# my_gearbox_project.net
KiCad netlist of a schematic drawn in EAGLE
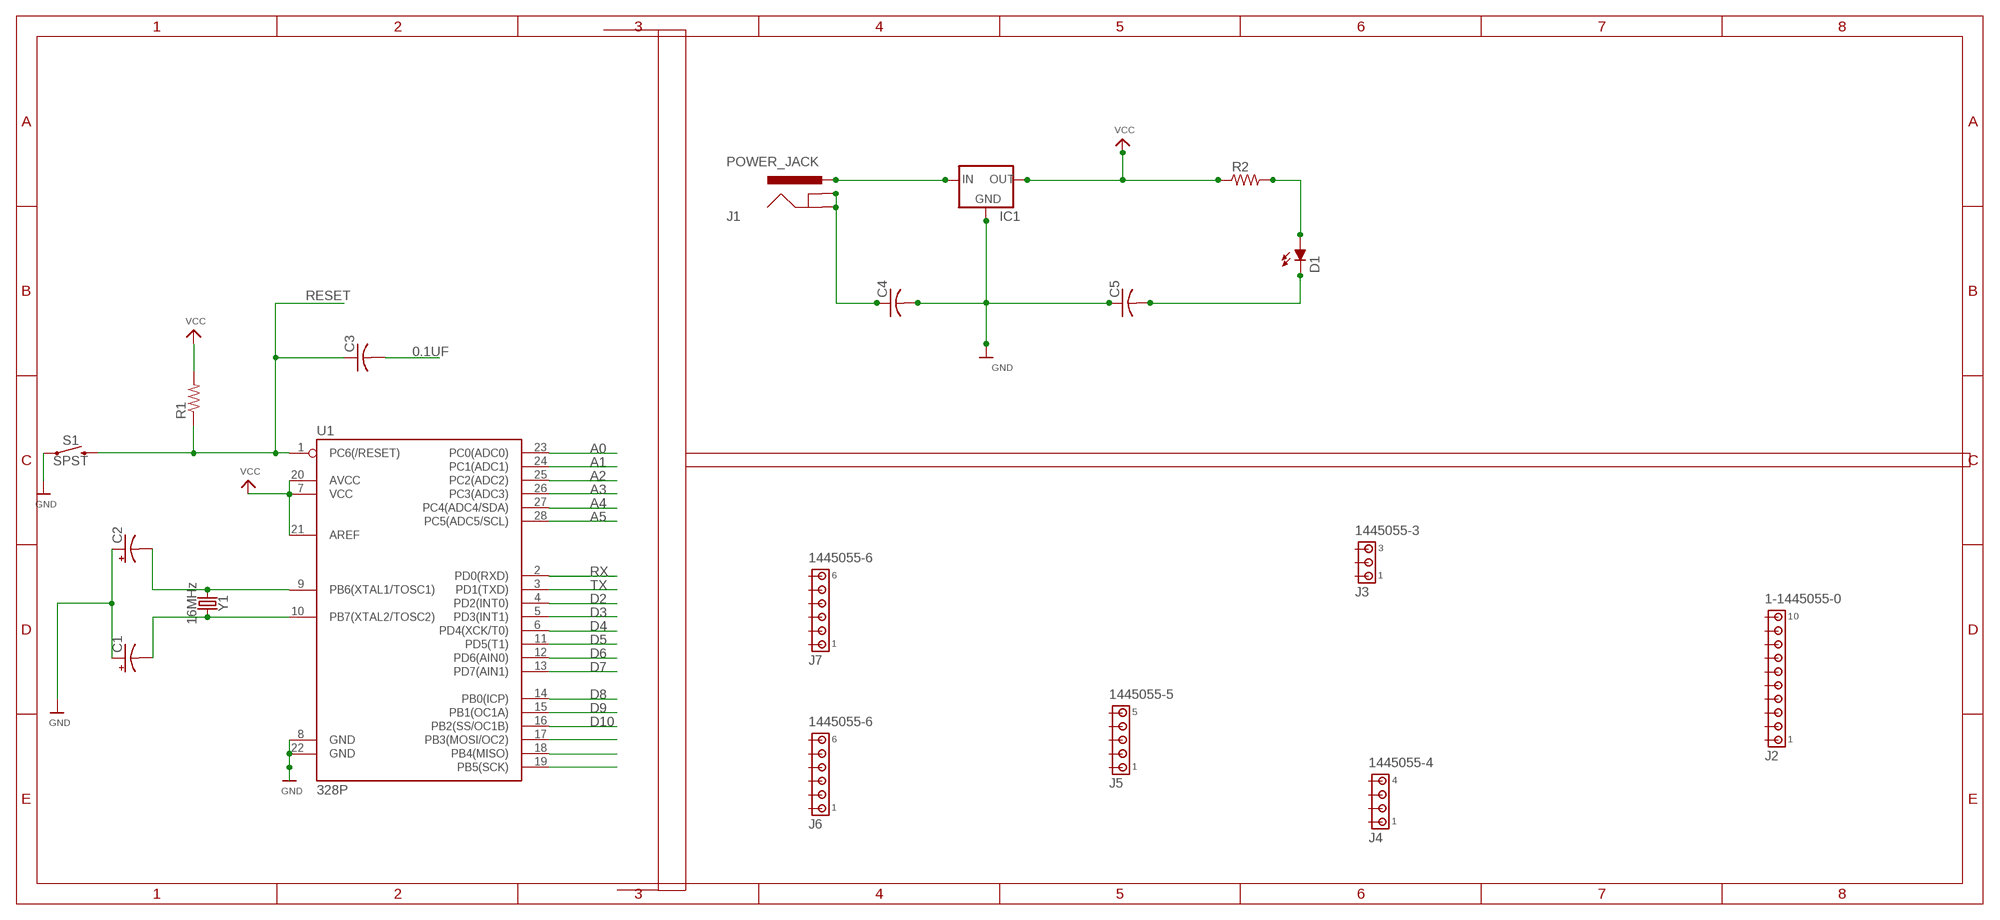
[diagram p0: schematic, sheet 1]

(export (version "E")
  (design (tool "Eeschema 10.0.6"))
  (components
    (comp (ref "C1")
      (value "CPOL-USE10-30")
      (footprint "eagle-import:EB30D")
      (libsource (lib "eagle-import") (part "CPOL-USE10-30"))
    )
    (comp (ref "C2")
      (value "CPOL-USE10-30")
      (footprint "eagle-import:EB30D")
      (libsource (lib "eagle-import") (part "CPOL-USE10-30"))
    )
    (comp (ref "C3")
      (value "C-US050-075X075")
      (footprint "eagle-import:C050-075X075")
      (libsource (lib "eagle-import") (part "C-US050-075X075"))
    )
    (comp (ref "C4")
      (value "C-US025-030X050")
      (footprint "eagle-import:C025-030X050")
      (libsource (lib "eagle-import") (part "C-US025-030X050"))
    )
    (comp (ref "C5")
      (value "C-US025-030X050")
      (footprint "eagle-import:C025-030X050")
      (libsource (lib "eagle-import") (part "C-US025-030X050"))
    )
    (comp (ref "D1")
      (value "LED_LEDCHIP-LED0603MP")
      (footprint "eagle-import:LED_CHIP-LED0603MP")
      (libsource (lib "eagle-import") (part "LED_LEDCHIP-LED0603MP"))
    )
    (comp (ref "IC1")
      (value "MCP1700INLINE")
      (footprint "eagle-import:TO92-INLINE")
      (libsource (lib "eagle-import") (part "MCP1700INLINE"))
    )
    (comp (ref "J1")
      (value "POWER_JACK")
      (footprint "eagle-import:POWER_JACK_PTH")
      (libsource (lib "eagle-import") (part "POWER_JACK"))
    )
    (comp (ref "J2")
      (value "1-1445055-0")
      (footprint "eagle-import:1445055-10")
      (libsource (lib "eagle-import") (part "1-1445055-0"))
    )
    (comp (ref "J3")
      (value "1445055-3")
      (footprint "eagle-import:1445055-3")
      (libsource (lib "eagle-import") (part "1445055-3"))
    )
    (comp (ref "J4")
      (value "1445055-4")
      (footprint "eagle-import:1445055-4")
      (libsource (lib "eagle-import") (part "1445055-4"))
    )
    (comp (ref "J5")
      (value "1445055-5")
      (footprint "eagle-import:1445055-5")
      (libsource (lib "eagle-import") (part "1445055-5"))
    )
    (comp (ref "J6")
      (value "1445055-6")
      (footprint "eagle-import:1445055-6")
      (libsource (lib "eagle-import") (part "1445055-6"))
    )
    (comp (ref "J7")
      (value "1445055-6")
      (footprint "eagle-import:1445055-6")
      (libsource (lib "eagle-import") (part "1445055-6"))
    )
    (comp (ref "R1")
      (value "R-US_R0402")
      (footprint "eagle-import:R0402")
      (libsource (lib "eagle-import") (part "R-US_R0402"))
    )
    (comp (ref "R2")
      (value "RC-MASTER-SMD_R_0603MP")
      (footprint "eagle-import:RC-MASTER-SMD_R0603MP")
      (libsource (lib "eagle-import") (part "RC-MASTER-SMD_R_0603MP"))
    )
    (comp (ref "S1")
      (value "SPST")
      (footprint "eagle-import:TACTILE_SWITCH_PTH_RIGHT_ANGLE_KIT")
      (libsource (lib "eagle-import") (part "MOMENTARY-SWITCH-SPST-PTH-RIGHT-ANGLE-KIT"))
    )
    (comp (ref "U1")
      (value "328P")
      (footprint "eagle-import:DIP28")
      (libsource (lib "eagle-import") (part "ATMEGA328P_PDIP"))
    )
    (comp (ref "Y1")
      (value "16MHz")
      (footprint "eagle-import:CRYSTAL-SMD-5X3.2-4PAD")
      (libsource (lib "eagle-import") (part "CRYSTAL-16MHZSMD-5X3.2"))
    )
  )
  (nets
    (net (code "1") (name "/0.1UF") (class "Default")
      (node (ref "C3") (pin "2") (pinfunction "2_2") (pintype "passive"))
    )
    (net (code "2") (name "/A0") (class "Default")
      (node (ref "U1") (pin "23") (pinfunction "PC0(ADC0)_23") (pintype "bidirectional"))
    )
    (net (code "3") (name "/A1") (class "Default")
      (node (ref "U1") (pin "24") (pinfunction "PC1(ADC1)_24") (pintype "bidirectional"))
    )
    (net (code "4") (name "/A2") (class "Default")
      (node (ref "U1") (pin "25") (pinfunction "PC2(ADC2)_25") (pintype "bidirectional"))
    )
    (net (code "5") (name "/A3") (class "Default")
      (node (ref "U1") (pin "26") (pinfunction "PC3(ADC3)_26") (pintype "bidirectional"))
    )
    (net (code "6") (name "/A4") (class "Default")
      (node (ref "U1") (pin "27") (pinfunction "PC4(ADC4/SDA)_27") (pintype "bidirectional"))
    )
    (net (code "7") (name "/A5") (class "Default")
      (node (ref "U1") (pin "28") (pinfunction "PC5(ADC5/SCL)_28") (pintype "bidirectional"))
    )
    (net (code "8") (name "/D2") (class "Default")
      (node (ref "U1") (pin "4") (pinfunction "PD2(INT0)_4") (pintype "bidirectional"))
    )
    (net (code "9") (name "/D3") (class "Default")
      (node (ref "U1") (pin "5") (pinfunction "PD3(INT1)_5") (pintype "bidirectional"))
    )
    (net (code "10") (name "/D4") (class "Default")
      (node (ref "U1") (pin "6") (pinfunction "PD4(XCK/T0)_6") (pintype "bidirectional"))
    )
    (net (code "11") (name "/D5") (class "Default")
      (node (ref "U1") (pin "11") (pinfunction "PD5(T1)_11") (pintype "bidirectional"))
    )
    (net (code "12") (name "/D6") (class "Default")
      (node (ref "U1") (pin "12") (pinfunction "PD6(AIN0)_12") (pintype "bidirectional"))
    )
    (net (code "13") (name "/D7") (class "Default")
      (node (ref "U1") (pin "13") (pinfunction "PD7(AIN1)_13") (pintype "bidirectional"))
    )
    (net (code "14") (name "/D8") (class "Default")
      (node (ref "U1") (pin "14") (pinfunction "PB0(ICP)_14") (pintype "bidirectional"))
    )
    (net (code "15") (name "/D9") (class "Default")
      (node (ref "U1") (pin "15") (pinfunction "PB1(OC1A)_15") (pintype "bidirectional"))
    )
    (net (code "16") (name "/D10") (class "Default")
      (node (ref "U1") (pin "16") (pinfunction "PB2(SS/OC1B)_16") (pintype "bidirectional"))
    )
    (net (code "17") (name "/RESET") (class "Default")
      (node (ref "C3") (pin "1") (pinfunction "1_1") (pintype "passive"))
      (node (ref "R1") (pin "1") (pinfunction "1_1") (pintype "passive"))
      (node (ref "S1") (pin "2") (pinfunction "2_2") (pintype "passive"))
      (node (ref "U1") (pin "1") (pinfunction "PC6(/RESET)_1") (pintype "bidirectional"))
    )
    (net (code "18") (name "/RX") (class "Default")
      (node (ref "U1") (pin "2") (pinfunction "PD0(RXD)_2") (pintype "bidirectional"))
    )
    (net (code "19") (name "/TX") (class "Default")
      (node (ref "U1") (pin "3") (pinfunction "PD1(TXD)_3") (pintype "bidirectional"))
    )
    (net (code "20") (name "GND") (class "Default")
      (node (ref "C1") (pin "+") (pinfunction "+_+") (pintype "passive"))
      (node (ref "C2") (pin "+") (pinfunction "+_+") (pintype "passive"))
      (node (ref "C4") (pin "2") (pinfunction "2_2") (pintype "passive"))
      (node (ref "C5") (pin "1") (pinfunction "1_1") (pintype "passive"))
      (node (ref "IC1") (pin "1") (pinfunction "GND_1") (pintype "input"))
      (node (ref "S1") (pin "1") (pinfunction "1_1") (pintype "passive"))
      (node (ref "U1") (pin "22") (pinfunction "GND_22") (pintype "bidirectional"))
      (node (ref "U1") (pin "8") (pinfunction "GND_8") (pintype "bidirectional"))
    )
    (net (code "21") (name "Net-(C4-Pad1)") (class "Default")
      (node (ref "C4") (pin "1") (pinfunction "1_1") (pintype "passive"))
      (node (ref "J1") (pin "GND") (pinfunction "GND_GND") (pintype "bidirectional"))
      (node (ref "J1") (pin "GNDBREAK") (pinfunction "GNDBREAK_GNDBREAK") (pintype "bidirectional"))
    )
    (net (code "22") (name "Net-(C5-Pad2)") (class "Default")
      (node (ref "C5") (pin "2") (pinfunction "2_2") (pintype "passive"))
      (node (ref "D1") (pin "C") (pinfunction "C_C") (pintype "passive"))
    )
    (net (code "23") (name "Net-(D1-PadA)") (class "Default")
      (node (ref "D1") (pin "A") (pinfunction "A_A") (pintype "passive"))
      (node (ref "R2") (pin "2") (pinfunction "2_2") (pintype "passive"))
    )
    (net (code "24") (name "Net-(IC1-IN)") (class "Default")
      (node (ref "IC1") (pin "2") (pinfunction "IN_2") (pintype "input"))
      (node (ref "J1") (pin "PWR") (pinfunction "PWR_PWR") (pintype "bidirectional"))
    )
    (net (code "25") (name "Net-(U1-PB6(XTAL1{slash}TOSC1))") (class "Default")
      (node (ref "C2") (pin "-") (pinfunction "-_-") (pintype "passive"))
      (node (ref "U1") (pin "9") (pinfunction "PB6(XTAL1/TOSC1)_9") (pintype "bidirectional"))
      (node (ref "Y1") (pin "1") (pinfunction "1_1") (pintype "passive"))
    )
    (net (code "26") (name "Net-(U1-PB7(XTAL2{slash}TOSC2))") (class "Default")
      (node (ref "C1") (pin "-") (pinfunction "-_-") (pintype "passive"))
      (node (ref "U1") (pin "10") (pinfunction "PB7(XTAL2/TOSC2)_10") (pintype "bidirectional"))
      (node (ref "Y1") (pin "3") (pinfunction "2_3") (pintype "passive"))
    )
    (net (code "27") (name "VCC") (class "Default")
      (node (ref "IC1") (pin "3") (pinfunction "OUT_3") (pintype "passive"))
      (node (ref "R1") (pin "2") (pinfunction "2_2") (pintype "passive"))
      (node (ref "R2") (pin "1") (pinfunction "1_1") (pintype "passive"))
      (node (ref "U1") (pin "20") (pinfunction "AVCC_20") (pintype "bidirectional"))
      (node (ref "U1") (pin "21") (pinfunction "AREF_21") (pintype "bidirectional"))
      (node (ref "U1") (pin "7") (pinfunction "VCC_7") (pintype "bidirectional"))
    )
    (net (code "28") (name "unconnected-(J2-Pad1)") (class "Default")
      (node (ref "J2") (pin "1") (pinfunction "1_1") (pintype "passive"))
    )
    (net (code "29") (name "unconnected-(J2-Pad2)") (class "Default")
      (node (ref "J2") (pin "2") (pinfunction "2_2") (pintype "passive"))
    )
    (net (code "30") (name "unconnected-(J2-Pad3)") (class "Default")
      (node (ref "J2") (pin "3") (pinfunction "3_3") (pintype "passive"))
    )
    (net (code "31") (name "unconnected-(J2-Pad4)") (class "Default")
      (node (ref "J2") (pin "4") (pinfunction "4_4") (pintype "passive"))
    )
    (net (code "32") (name "unconnected-(J2-Pad5)") (class "Default")
      (node (ref "J2") (pin "5") (pinfunction "5_5") (pintype "passive"))
    )
    (net (code "33") (name "unconnected-(J2-Pad6)") (class "Default")
      (node (ref "J2") (pin "6") (pinfunction "6_6") (pintype "passive"))
    )
    (net (code "34") (name "unconnected-(J2-Pad7)") (class "Default")
      (node (ref "J2") (pin "7") (pinfunction "7_7") (pintype "passive"))
    )
    (net (code "35") (name "unconnected-(J2-Pad8)") (class "Default")
      (node (ref "J2") (pin "8") (pinfunction "8_8") (pintype "passive"))
    )
    (net (code "36") (name "unconnected-(J2-Pad9)") (class "Default")
      (node (ref "J2") (pin "9") (pinfunction "9_9") (pintype "passive"))
    )
    (net (code "37") (name "unconnected-(J2-Pad10)") (class "Default")
      (node (ref "J2") (pin "10") (pinfunction "10_10") (pintype "passive"))
    )
    (net (code "38") (name "unconnected-(J3-Pad1)") (class "Default")
      (node (ref "J3") (pin "1") (pinfunction "1_1") (pintype "passive"))
    )
    (net (code "39") (name "unconnected-(J3-Pad2)") (class "Default")
      (node (ref "J3") (pin "2") (pinfunction "2_2") (pintype "passive"))
    )
    (net (code "40") (name "unconnected-(J3-Pad3)") (class "Default")
      (node (ref "J3") (pin "3") (pinfunction "3_3") (pintype "passive"))
    )
    (net (code "41") (name "unconnected-(J4-Pad1)") (class "Default")
      (node (ref "J4") (pin "1") (pinfunction "1_1") (pintype "passive"))
    )
    (net (code "42") (name "unconnected-(J4-Pad2)") (class "Default")
      (node (ref "J4") (pin "2") (pinfunction "2_2") (pintype "passive"))
    )
    (net (code "43") (name "unconnected-(J4-Pad3)") (class "Default")
      (node (ref "J4") (pin "3") (pinfunction "3_3") (pintype "passive"))
    )
    (net (code "44") (name "unconnected-(J4-Pad4)") (class "Default")
      (node (ref "J4") (pin "4") (pinfunction "4_4") (pintype "passive"))
    )
    (net (code "45") (name "unconnected-(J5-Pad1)") (class "Default")
      (node (ref "J5") (pin "1") (pinfunction "1_1") (pintype "passive"))
    )
    (net (code "46") (name "unconnected-(J5-Pad2)") (class "Default")
      (node (ref "J5") (pin "2") (pinfunction "2_2") (pintype "passive"))
    )
    (net (code "47") (name "unconnected-(J5-Pad3)") (class "Default")
      (node (ref "J5") (pin "3") (pinfunction "3_3") (pintype "passive"))
    )
    (net (code "48") (name "unconnected-(J5-Pad4)") (class "Default")
      (node (ref "J5") (pin "4") (pinfunction "4_4") (pintype "passive"))
    )
    (net (code "49") (name "unconnected-(J5-Pad5)") (class "Default")
      (node (ref "J5") (pin "5") (pinfunction "5_5") (pintype "passive"))
    )
    (net (code "50") (name "unconnected-(J6-Pad1)") (class "Default")
      (node (ref "J6") (pin "1") (pinfunction "1_1") (pintype "passive"))
    )
    (net (code "51") (name "unconnected-(J6-Pad2)") (class "Default")
      (node (ref "J6") (pin "2") (pinfunction "2_2") (pintype "passive"))
    )
    (net (code "52") (name "unconnected-(J6-Pad3)") (class "Default")
      (node (ref "J6") (pin "3") (pinfunction "3_3") (pintype "passive"))
    )
    (net (code "53") (name "unconnected-(J6-Pad4)") (class "Default")
      (node (ref "J6") (pin "4") (pinfunction "4_4") (pintype "passive"))
    )
    (net (code "54") (name "unconnected-(J6-Pad5)") (class "Default")
      (node (ref "J6") (pin "5") (pinfunction "5_5") (pintype "passive"))
    )
    (net (code "55") (name "unconnected-(J6-Pad6)") (class "Default")
      (node (ref "J6") (pin "6") (pinfunction "6_6") (pintype "passive"))
    )
    (net (code "56") (name "unconnected-(J7-Pad1)") (class "Default")
      (node (ref "J7") (pin "1") (pinfunction "1_1") (pintype "passive"))
    )
    (net (code "57") (name "unconnected-(J7-Pad2)") (class "Default")
      (node (ref "J7") (pin "2") (pinfunction "2_2") (pintype "passive"))
    )
    (net (code "58") (name "unconnected-(J7-Pad3)") (class "Default")
      (node (ref "J7") (pin "3") (pinfunction "3_3") (pintype "passive"))
    )
    (net (code "59") (name "unconnected-(J7-Pad4)") (class "Default")
      (node (ref "J7") (pin "4") (pinfunction "4_4") (pintype "passive"))
    )
    (net (code "60") (name "unconnected-(J7-Pad5)") (class "Default")
      (node (ref "J7") (pin "5") (pinfunction "5_5") (pintype "passive"))
    )
    (net (code "61") (name "unconnected-(J7-Pad6)") (class "Default")
      (node (ref "J7") (pin "6") (pinfunction "6_6") (pintype "passive"))
    )
    (net (code "62") (name "unconnected-(U1-PB3(MOSI{slash}OC2)-Pad17)") (class "Default")
      (node (ref "U1") (pin "17") (pinfunction "PB3(MOSI/OC2)_17") (pintype "bidirectional"))
    )
    (net (code "63") (name "unconnected-(U1-PB4(MISO)-Pad18)") (class "Default")
      (node (ref "U1") (pin "18") (pinfunction "PB4(MISO)_18") (pintype "bidirectional"))
    )
    (net (code "64") (name "unconnected-(U1-PB5(SCK)-Pad19)") (class "Default")
      (node (ref "U1") (pin "19") (pinfunction "PB5(SCK)_19") (pintype "bidirectional"))
    )
  )
)
